# schematic.net
KiCad netlist of a schematic drawn in Altium Designer
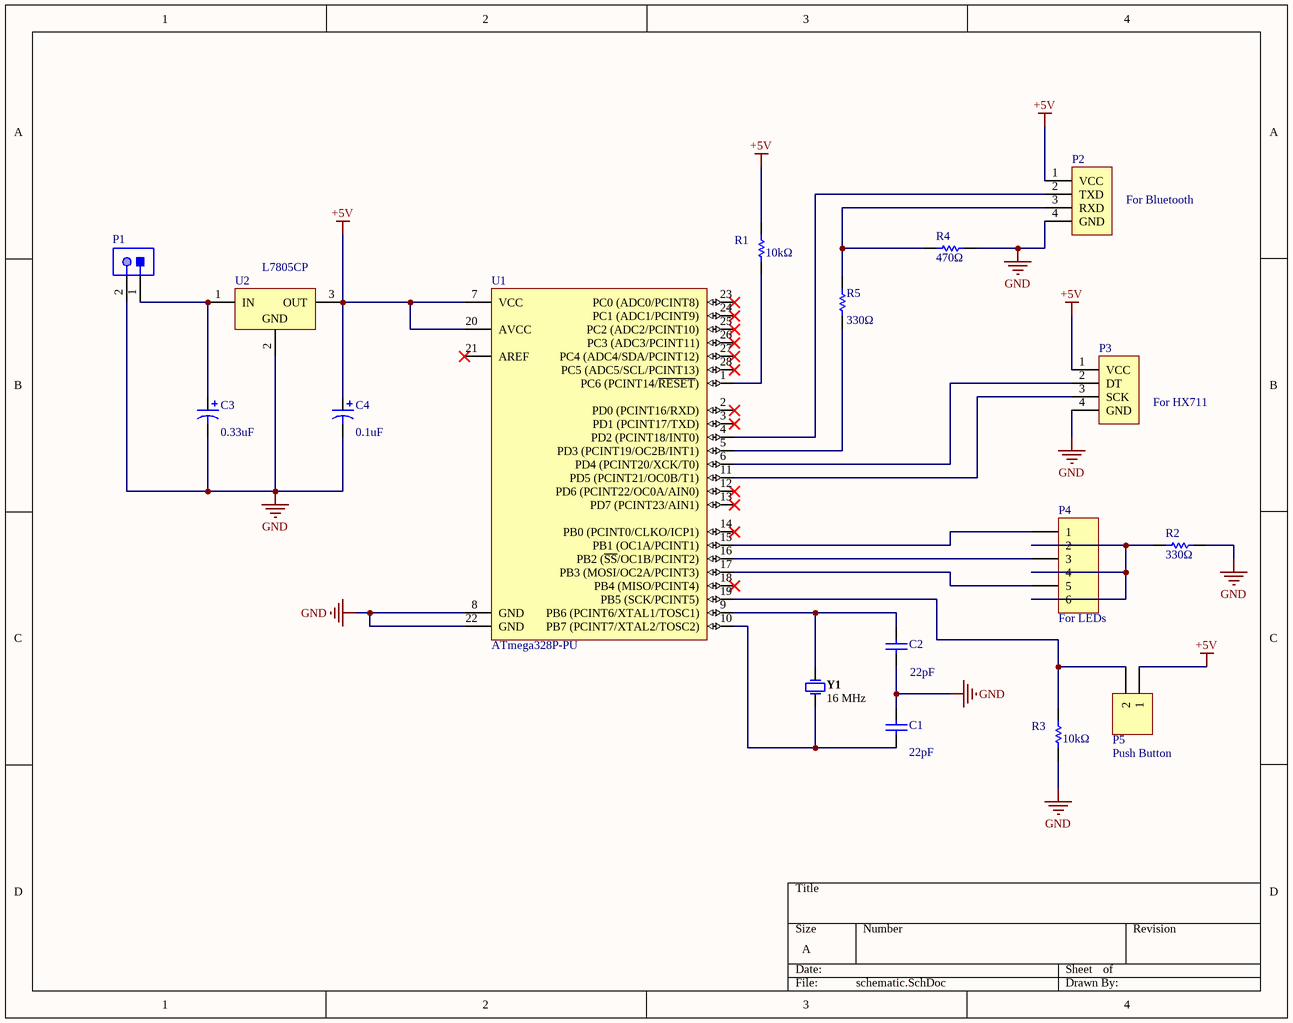
[diagram p0: schematic.SchDoc]

(export (version "E")
  (design (tool "Eeschema 10.0.6"))
  (components
    (comp (ref "C1")
      (value "22pF")
      (footprint "RAD-0.3")
      (description "Capacitor")
      (fields (field (name "Comment") "Cap") (field (name "PUBLISHER") "Altium Limited"))
      (libsource (lib "Miscellaneous Devices") (part "Cap"))
    )
    (comp (ref "C2")
      (value "22pF")
      (footprint "RAD-0.3")
      (description "Capacitor")
      (fields (field (name "Comment") "Cap") (field (name "PUBLISHER") "Altium Limited"))
      (libsource (lib "Miscellaneous Devices") (part "Cap"))
    )
    (comp (ref "C3")
      (value "0.33uF")
      (footprint "RB7.6-15")
      (description "Polarized Capacitor (Radial)")
      (fields (field (name "Comment") "Cap Pol1") (field (name "PUBLISHER") "Altium Limited"))
      (libsource (lib "Miscellaneous Devices") (part "Cap Pol1"))
    )
    (comp (ref "C4")
      (value "0.1uF")
      (footprint "RB7.6-15")
      (description "Polarized Capacitor (Radial)")
      (fields (field (name "Comment") "Cap Pol1") (field (name "PUBLISHER") "Altium Limited"))
      (libsource (lib "Miscellaneous Devices") (part "Cap Pol1"))
    )
    (comp (ref "P1")
      (value "61900211021")
      (footprint "61900211021")
      (description "Male Bottom Locking Header WR-WTB, THT, Right Angled, pitch 2.54 mm, 1 x 2 position")
      (fields (field (name "MANUFACTURER") "Wurth Elektronik") (field (name "PUBLISHER") "WurthElektronik"))
      (libsource (lib "Altium Content Vault") (part "WE-CN-1P-M-R2"))
    )
    (comp (ref "P2")
      (value "For Bluetooth")
      (footprint "HDR1X4")
      (description "Header, 4-Pin")
      (fields (field (name "PUBLISHER") "Altium Limited"))
      (libsource (lib "Miscellaneous Connectors") (part "Header 4"))
    )
    (comp (ref "P3")
      (value "For HX711")
      (footprint "HDR1X4")
      (description "Header, 4-Pin")
      (fields (field (name "PUBLISHER") "Altium Limited"))
      (libsource (lib "Miscellaneous Connectors") (part "Header 4"))
    )
    (comp (ref "P4")
      (value "For LEDs")
      (footprint "HDR1X6")
      (description "Header, 6-Pin")
      (fields (field (name "PUBLISHER") "Altium Limited"))
      (libsource (lib "Miscellaneous Connectors") (part "Header 6"))
    )
    (comp (ref "P5")
      (value "Push Button")
      (footprint "HDR1X2")
      (description "Header, 2-Pin")
      (fields (field (name "PUBLISHER") "Altium Limited"))
      (libsource (lib "Miscellaneous Connectors") (part "Header 2"))
    )
    (comp (ref "R1")
      (value "10kΩ")
      (footprint "AXIAL-0.3")
      (description "Resistor")
      (fields (field (name "Comment") "Res1") (field (name "PUBLISHER") "Altium Limited"))
      (libsource (lib "Miscellaneous Devices") (part "Res1"))
    )
    (comp (ref "R2")
      (value "330Ω")
      (footprint "AXIAL-0.3")
      (description "Resistor")
      (fields (field (name "Comment") "Res1") (field (name "PUBLISHER") "Altium Limited"))
      (libsource (lib "Miscellaneous Devices") (part "Res1"))
    )
    (comp (ref "R3")
      (value "10kΩ")
      (footprint "AXIAL-0.3")
      (description "Resistor")
      (fields (field (name "Comment") "Res1") (field (name "PUBLISHER") "Altium Limited"))
      (libsource (lib "Miscellaneous Devices") (part "Res1"))
    )
    (comp (ref "R4")
      (value "470Ω")
      (footprint "AXIAL-0.3")
      (description "Resistor")
      (fields (field (name "Comment") "Res1") (field (name "PUBLISHER") "Altium Limited"))
      (libsource (lib "Miscellaneous Devices") (part "Res1"))
    )
    (comp (ref "R5")
      (value "330Ω")
      (footprint "AXIAL-0.3")
      (description "Resistor")
      (fields (field (name "Comment") "Res1") (field (name "PUBLISHER") "Altium Limited"))
      (libsource (lib "Miscellaneous Devices") (part "Res1"))
    )
    (comp (ref "U1")
      (value "ATmega328P-PU")
      (footprint "28P3")
      (libsource (lib "Altium Content Vault") (part "MC-8B-ATM48-IL28"))
    )
    (comp (ref "U2")
      (value "L7805CP")
      (footprint "TO220FP")
      (description "Positive Voltage Regulator, 5V, 3-Pin TO-220FP")
      (libsource (lib "Altium Content Vault") (part "PM-REG-L4940-SIL3"))
    )
    (comp (ref "Y1")
      (value "16 MHz")
      (footprint "FOX-FOXSLF160-20")
      (description "Resistance Weld Thru-Hole Crystal, 16 MHz, -20 to 70 degC, 2-Pin THD, RoHS, Bulk")
      (fields (field (name "TOLERANCE") "1%"))
      (libsource (lib "Altium Content Vault") (part "XTAL-1-2-2"))
    )
  )
  (nets
    (net (code "1") (name "+5V") (class "Default")
      (node (ref "C4") (pin "1") (pinfunction "1_1") (pintype "passive"))
      (node (ref "P2") (pin "1") (pinfunction "VCC_1") (pintype "passive"))
      (node (ref "P3") (pin "1") (pinfunction "VCC_1") (pintype "passive"))
      (node (ref "P5") (pin "1") (pinfunction "1_1") (pintype "passive"))
      (node (ref "R1") (pin "1") (pinfunction "1_1") (pintype "passive"))
      (node (ref "U1") (pin "20") (pinfunction "AVCC_20") (pintype "power_in"))
      (node (ref "U1") (pin "7") (pinfunction "VCC_7") (pintype "power_in"))
      (node (ref "U2") (pin "3") (pinfunction "OUT_3") (pintype "power_in"))
    )
    (net (code "2") (name "GND") (class "Default")
      (node (ref "C1") (pin "2") (pinfunction "2_2") (pintype "passive"))
      (node (ref "C2") (pin "2") (pinfunction "2_2") (pintype "passive"))
      (node (ref "C3") (pin "2") (pinfunction "2_2") (pintype "passive"))
      (node (ref "C4") (pin "2") (pinfunction "2_2") (pintype "passive"))
      (node (ref "P1") (pin "2") (pinfunction "2_2") (pintype "passive"))
      (node (ref "P2") (pin "4") (pinfunction "GND_4") (pintype "passive"))
      (node (ref "P3") (pin "4") (pinfunction "GND_4") (pintype "passive"))
      (node (ref "R2") (pin "2") (pinfunction "2_2") (pintype "passive"))
      (node (ref "R3") (pin "2") (pinfunction "2_2") (pintype "passive"))
      (node (ref "R4") (pin "2") (pinfunction "2_2") (pintype "passive"))
      (node (ref "U1") (pin "22") (pinfunction "GND_22") (pintype "power_in"))
      (node (ref "U1") (pin "8") (pinfunction "GND_8") (pintype "power_in"))
      (node (ref "U2") (pin "2") (pinfunction "GND_2") (pintype "power_in"))
    )
    (net (code "3") (name "Net-(P2-DT)") (class "Default")
      (node (ref "P2") (pin "2") (pinfunction "DT_2") (pintype "passive"))
      (node (ref "U1") (pin "4") (pinfunction "PD2_(PCINT18/INT0)_4") (pintype "bidirectional"))
    )
    (net (code "4") (name "Net-(P2-SCK)") (class "Default")
      (node (ref "P2") (pin "3") (pinfunction "SCK_3") (pintype "passive"))
      (node (ref "R4") (pin "1") (pinfunction "1_1") (pintype "passive"))
      (node (ref "R5") (pin "2") (pinfunction "2_2") (pintype "passive"))
    )
    (net (code "5") (name "Net-(P3-DT)") (class "Default")
      (node (ref "P3") (pin "2") (pinfunction "DT_2") (pintype "passive"))
      (node (ref "U1") (pin "6") (pinfunction "PD4_(PCINT20/XCK/T0)_6") (pintype "bidirectional"))
    )
    (net (code "6") (name "Net-(P3-SCK)") (class "Default")
      (node (ref "P3") (pin "3") (pinfunction "SCK_3") (pintype "passive"))
      (node (ref "U1") (pin "11") (pinfunction "PD5_(PCINT21/OC0B/T1)_11") (pintype "bidirectional"))
    )
    (net (code "7") (name "Net-(P4-Pad2)") (class "Default")
      (node (ref "P4") (pin "2") (pinfunction "2_2") (pintype "passive"))
      (node (ref "P4") (pin "4") (pinfunction "4_4") (pintype "passive"))
      (node (ref "P4") (pin "6") (pinfunction "6_6") (pintype "passive"))
      (node (ref "R2") (pin "1") (pinfunction "1_1") (pintype "passive"))
    )
    (net (code "8") (name "Net-(U1-PB1_(OC1A{slash}PCINT1))") (class "Default")
      (node (ref "P4") (pin "1") (pinfunction "1_1") (pintype "passive"))
      (node (ref "U1") (pin "15") (pinfunction "PB1_(OC1A/PCINT1)_15") (pintype "bidirectional"))
    )
    (net (code "9") (name "Net-(U1-PB2_(~{SS}{slash}OC1B{slash}PCINT2))") (class "Default")
      (node (ref "P4") (pin "3") (pinfunction "3_3") (pintype "passive"))
      (node (ref "U1") (pin "16") (pinfunction "PB2_(~{SS}/OC1B/PCINT2)_16") (pintype "bidirectional"))
    )
    (net (code "10") (name "Net-(U1-PB3_(MOSI{slash}OC2A{slash}PCINT3))") (class "Default")
      (node (ref "P4") (pin "5") (pinfunction "5_5") (pintype "passive"))
      (node (ref "U1") (pin "17") (pinfunction "PB3_(MOSI/OC2A/PCINT3)_17") (pintype "bidirectional"))
    )
    (net (code "11") (name "Net-(U1-PB5_(SCK{slash}PCINT5))") (class "Default")
      (node (ref "P5") (pin "2") (pinfunction "2_2") (pintype "passive"))
      (node (ref "R3") (pin "1") (pinfunction "1_1") (pintype "passive"))
      (node (ref "U1") (pin "19") (pinfunction "PB5_(SCK/PCINT5)_19") (pintype "bidirectional"))
    )
    (net (code "12") (name "Net-(U1-PB6_(PCINT6{slash}XTAL1{slash}TOSC1))") (class "Default")
      (node (ref "C2") (pin "1") (pinfunction "1_1") (pintype "passive"))
      (node (ref "U1") (pin "9") (pinfunction "PB6_(PCINT6/XTAL1/TOSC1)_9") (pintype "bidirectional"))
      (node (ref "Y1") (pin "1") (pinfunction "1_1") (pintype "passive"))
    )
    (net (code "13") (name "Net-(U1-PB7_(PCINT7{slash}XTAL2{slash}TOSC2))") (class "Default")
      (node (ref "C1") (pin "1") (pinfunction "1_1") (pintype "passive"))
      (node (ref "U1") (pin "10") (pinfunction "PB7_(PCINT7/XTAL2/TOSC2)_10") (pintype "bidirectional"))
      (node (ref "Y1") (pin "2") (pinfunction "2_2") (pintype "passive"))
    )
    (net (code "14") (name "Net-(U1-PC6_(PCINT14{slash}~{RESET}))") (class "Default")
      (node (ref "R1") (pin "2") (pinfunction "2_2") (pintype "passive"))
      (node (ref "U1") (pin "1") (pinfunction "PC6_(PCINT14/~{RESET})_1") (pintype "bidirectional"))
    )
    (net (code "15") (name "Net-(U1-PD3_(PCINT19{slash}OC2B{slash}INT1))") (class "Default")
      (node (ref "R5") (pin "1") (pinfunction "1_1") (pintype "passive"))
      (node (ref "U1") (pin "5") (pinfunction "PD3_(PCINT19/OC2B/INT1)_5") (pintype "bidirectional"))
    )
    (net (code "16") (name "Net-(U2-IN)") (class "Default")
      (node (ref "C3") (pin "1") (pinfunction "1_1") (pintype "passive"))
      (node (ref "P1") (pin "1") (pinfunction "1_1") (pintype "passive"))
      (node (ref "U2") (pin "1") (pinfunction "IN_1") (pintype "power_in"))
    )
    (net (code "17") (name "unconnected-(U1-AREF-Pad21)") (class "Default")
      (node (ref "U1") (pin "21") (pinfunction "AREF_21") (pintype "power_in+no_connect"))
    )
    (net (code "18") (name "unconnected-(U1-PB0_(PCINT0{slash}CLKO{slash}ICP1)-Pad14)") (class "Default")
      (node (ref "U1") (pin "14") (pinfunction "PB0_(PCINT0/CLKO/ICP1)_14") (pintype "bidirectional+no_connect"))
    )
    (net (code "19") (name "unconnected-(U1-PB4_(MISO{slash}PCINT4)-Pad18)") (class "Default")
      (node (ref "U1") (pin "18") (pinfunction "PB4_(MISO/PCINT4)_18") (pintype "bidirectional+no_connect"))
    )
    (net (code "20") (name "unconnected-(U1-PC0_(ADC0{slash}PCINT8)-Pad23)") (class "Default")
      (node (ref "U1") (pin "23") (pinfunction "PC0_(ADC0/PCINT8)_23") (pintype "bidirectional+no_connect"))
    )
    (net (code "21") (name "unconnected-(U1-PC1_(ADC1{slash}PCINT9)-Pad24)") (class "Default")
      (node (ref "U1") (pin "24") (pinfunction "PC1_(ADC1/PCINT9)_24") (pintype "bidirectional+no_connect"))
    )
    (net (code "22") (name "unconnected-(U1-PC2_(ADC2{slash}PCINT10)-Pad25)") (class "Default")
      (node (ref "U1") (pin "25") (pinfunction "PC2_(ADC2/PCINT10)_25") (pintype "bidirectional+no_connect"))
    )
    (net (code "23") (name "unconnected-(U1-PC3_(ADC3{slash}PCINT11)-Pad26)") (class "Default")
      (node (ref "U1") (pin "26") (pinfunction "PC3_(ADC3/PCINT11)_26") (pintype "bidirectional+no_connect"))
    )
    (net (code "24") (name "unconnected-(U1-PC4_(ADC4{slash}SDA{slash}PCINT12)-Pad27)") (class "Default")
      (node (ref "U1") (pin "27") (pinfunction "PC4_(ADC4/SDA/PCINT12)_27") (pintype "bidirectional+no_connect"))
    )
    (net (code "25") (name "unconnected-(U1-PC5_(ADC5{slash}SCL{slash}PCINT13)-Pad28)") (class "Default")
      (node (ref "U1") (pin "28") (pinfunction "PC5_(ADC5/SCL/PCINT13)_28") (pintype "bidirectional+no_connect"))
    )
    (net (code "26") (name "unconnected-(U1-PD0_(PCINT16{slash}RXD)-Pad2)") (class "Default")
      (node (ref "U1") (pin "2") (pinfunction "PD0_(PCINT16/RXD)_2") (pintype "bidirectional+no_connect"))
    )
    (net (code "27") (name "unconnected-(U1-PD1_(PCINT17{slash}TXD)-Pad3)") (class "Default")
      (node (ref "U1") (pin "3") (pinfunction "PD1_(PCINT17/TXD)_3") (pintype "bidirectional+no_connect"))
    )
    (net (code "28") (name "unconnected-(U1-PD6_(PCINT22{slash}OC0A{slash}AIN0)-Pad12)") (class "Default")
      (node (ref "U1") (pin "12") (pinfunction "PD6_(PCINT22/OC0A/AIN0)_12") (pintype "bidirectional+no_connect"))
    )
    (net (code "29") (name "unconnected-(U1-PD7_(PCINT23{slash}AIN1)-Pad13)") (class "Default")
      (node (ref "U1") (pin "13") (pinfunction "PD7_(PCINT23/AIN1)_13") (pintype "bidirectional+no_connect"))
    )
  )
)
